# Control.net
KiCad netlist of a schematic drawn in Altium Designer
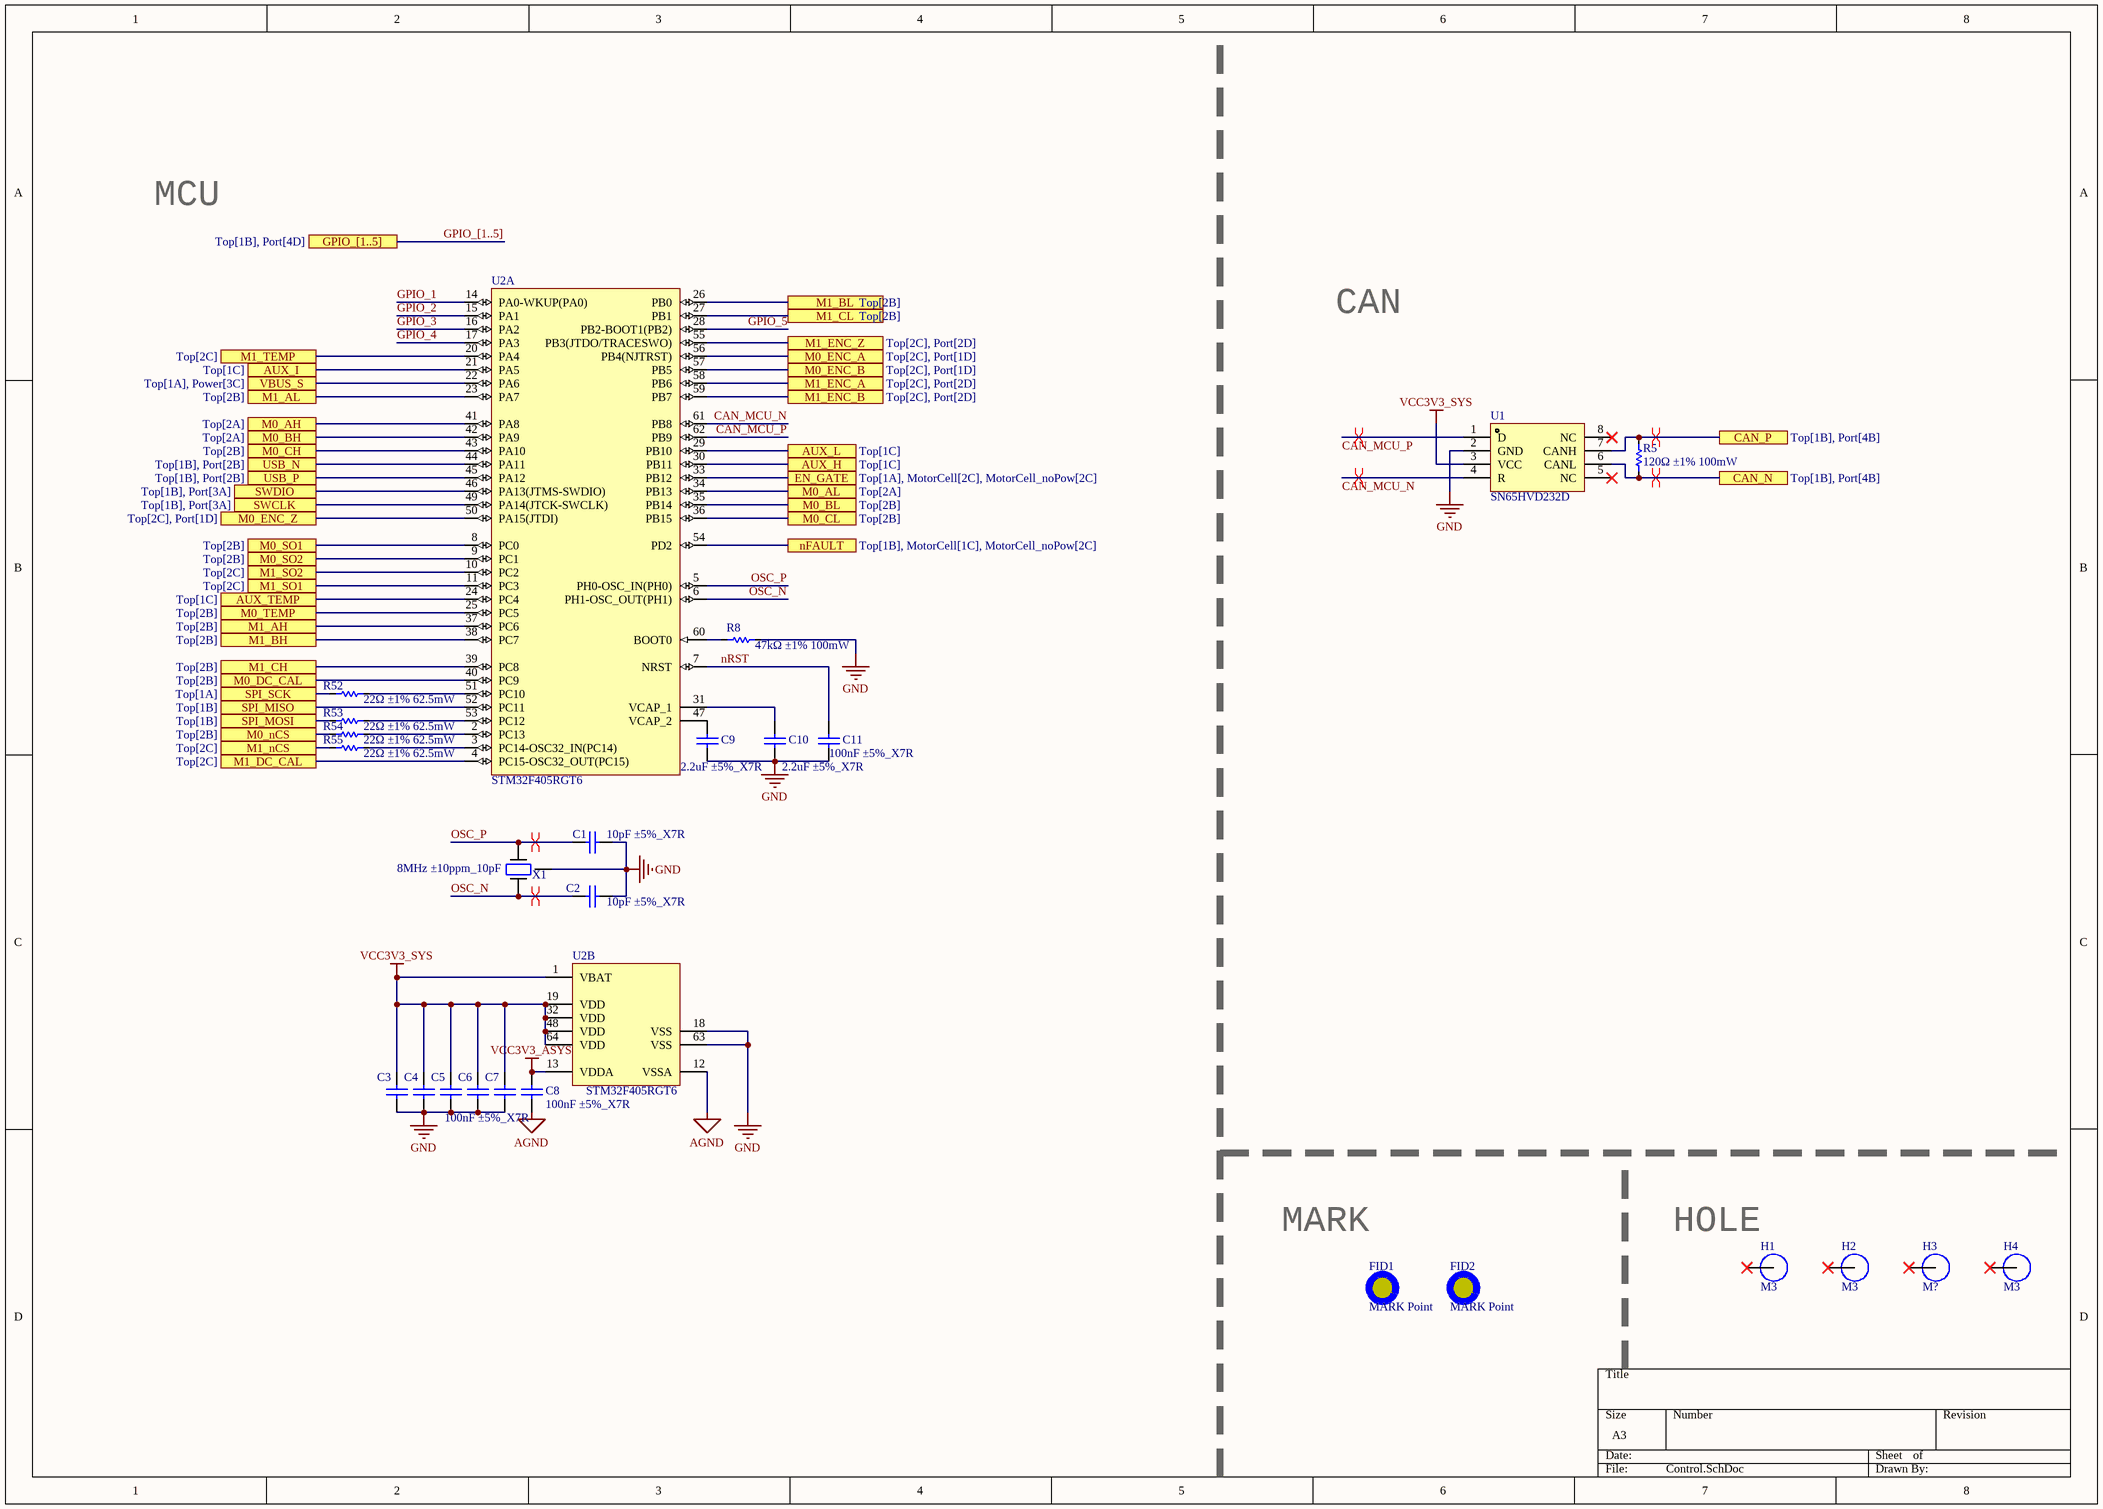
[diagram p0: Control.SchDoc]

(export (version "E")
  (design (tool "Eeschema 10.0.6"))
  (components
    (comp (ref "C1")
      (value "10pF ±5%_X7R")
      (footprint "C0402")
      (description "Capacitor")
      (fields (field (name "PUBLISHER") "Altium Limited"))
      (libsource (lib "Component") (part "Cap"))
    )
    (comp (ref "C2")
      (value "10pF ±5%_X7R")
      (footprint "C0402")
      (description "Capacitor")
      (fields (field (name "PUBLISHER") "Altium Limited"))
      (libsource (lib "Component") (part "Cap"))
    )
    (comp (ref "C3")
      (value "100nF ±5%_X7R")
      (footprint "C0402")
      (description "Capacitor")
      (fields (field (name "PUBLISHER") "Altium Limited"))
      (libsource (lib "Component") (part "Cap"))
    )
    (comp (ref "C4")
      (value "100nF ±5%_X7R")
      (footprint "C0402")
      (description "Capacitor")
      (fields (field (name "PUBLISHER") "Altium Limited"))
      (libsource (lib "Component") (part "Cap"))
    )
    (comp (ref "C5")
      (value "F ±5%_X7R")
      (footprint "C0402")
      (description "Capacitor")
      (fields (field (name "PUBLISHER") "Altium Limited"))
      (libsource (lib "Component") (part "Cap"))
    )
    (comp (ref "C6")
      (value "F ±5%_X7R")
      (footprint "C0402")
      (description "Capacitor")
      (fields (field (name "PUBLISHER") "Altium Limited"))
      (libsource (lib "Component") (part "Cap"))
    )
    (comp (ref "C7")
      (value "F ±5%_X7R")
      (footprint "C0402")
      (description "Capacitor")
      (fields (field (name "PUBLISHER") "Altium Limited"))
      (libsource (lib "Component") (part "Cap"))
    )
    (comp (ref "C8")
      (value "100nF ±5%_X7R")
      (footprint "C0402")
      (description "Capacitor")
      (fields (field (name "PUBLISHER") "Altium Limited"))
      (libsource (lib "Component") (part "Cap"))
    )
    (comp (ref "C9")
      (value "2.2uF ±5%_X7R")
      (footprint "C0603")
      (description "Capacitor")
      (fields (field (name "PUBLISHER") "Altium Limited"))
      (libsource (lib "Component") (part "Cap"))
    )
    (comp (ref "C10")
      (value "2.2uF ±5%_X7R")
      (footprint "C0603")
      (description "Capacitor")
      (fields (field (name "PUBLISHER") "Altium Limited"))
      (libsource (lib "Component") (part "Cap"))
    )
    (comp (ref "C11")
      (value "100nF ±5%_X7R")
      (footprint "C0402")
      (description "Capacitor")
      (fields (field (name "PUBLISHER") "Altium Limited"))
      (libsource (lib "Component") (part "Cap"))
    )
    (comp (ref "FID1")
      (value "MARK Point")
      (footprint "FIDUCIAL")
      (description "1mm Fiducial with 2mm soldermask, 3mm keepout")
      (libsource (lib "Component") (part "FIDUCIAL"))
    )
    (comp (ref "FID2")
      (value "MARK Point")
      (footprint "FIDUCIAL")
      (description "1mm Fiducial with 2mm soldermask, 3mm keepout")
      (libsource (lib "Component") (part "FIDUCIAL"))
    )
    (comp (ref "H1")
      (value "M3")
      (footprint "M3_NPTH")
      (description "Hole without copper")
      (libsource (lib "Component") (part "NPTH"))
    )
    (comp (ref "H2")
      (value "M3")
      (footprint "M3_NPTH")
      (description "Hole without copper")
      (libsource (lib "Component") (part "NPTH"))
    )
    (comp (ref "H3")
      (value "M?")
      (footprint "M3_NPTH")
      (description "Hole without copper")
      (libsource (lib "Component") (part "NPTH"))
    )
    (comp (ref "H4")
      (value "M3")
      (footprint "M3_NPTH")
      (description "Hole without copper")
      (libsource (lib "Component") (part "NPTH"))
    )
    (comp (ref "R5")
      (value "120Ω ±1% 100mW")
      (footprint "R0603")
      (description "Resistor")
      (fields (field (name "PUBLISHER") "Altium Limited"))
      (libsource (lib "Component") (part "Res"))
    )
    (comp (ref "R8")
      (value "47kΩ ±1% 100mW")
      (footprint "R0402")
      (description "Resistor")
      (fields (field (name "PUBLISHER") "Altium Limited"))
      (libsource (lib "Component") (part "Res"))
    )
    (comp (ref "R52")
      (value "22Ω ±1% 62.5mW")
      (footprint "R0402")
      (description "Resistor")
      (fields (field (name "PUBLISHER") "Altium Limited"))
      (libsource (lib "Component") (part "Res"))
    )
    (comp (ref "R53")
      (value "22Ω ±1% 62.5mW")
      (footprint "R0402")
      (description "Resistor")
      (fields (field (name "PUBLISHER") "Altium Limited"))
      (libsource (lib "Component") (part "Res"))
    )
    (comp (ref "R54")
      (value "22Ω ±1% 62.5mW")
      (footprint "R0402")
      (description "Resistor")
      (fields (field (name "PUBLISHER") "Altium Limited"))
      (libsource (lib "Component") (part "Res"))
    )
    (comp (ref "R55")
      (value "22Ω ±1% 62.5mW")
      (footprint "R0402")
      (description "Resistor")
      (fields (field (name "PUBLISHER") "Altium Limited"))
      (libsource (lib "Component") (part "Res"))
    )
    (comp (ref "U1")
      (value "SN65HVD232D")
      (footprint "SOIC127P600X175-8N")
      (fields (field (name "MANUFACTURER") "Texas Instruments"))
      (libsource (lib "IC") (part "SN65HVD232D"))
    )
    (comp (ref "U2")
      (value "STM32F405RGT6")
      (footprint "STM-LQFP64_N")
      (fields (field (name "MANUFACTURER") "STMicroelectronics"))
      (libsource (lib "STMicroelectronics STM32 F4") (part "STM32F405RGT6"))
    )
    (comp (ref "X1")
      (value "8MHz ±10ppm_10pF")
      (footprint "CRYSTAL_3225")
      (description "Crystal 8MHz ±10ppm 10pF 200 Ohm -10°C ~ 60°C Surface Mount 4-SMD, No Lead (DFN, LCC)")
      (fields
        (field (name "MANUFACTURER") "Abracon LLC")
        (field (name "MANUFACTURER PART NUMBER") "ABM3B-8.000MHZ-10-1-U-T")
      )
      (libsource (lib "Component") (part "CRYSTAL"))
    )
  )
  (nets
    (net (code "1") (name "/AUX_H") (class "Default")
      (node (ref "U2") (pin "30") (pinfunction "PB11_30") (pintype "bidirectional"))
    )
    (net (code "2") (name "/AUX_I") (class "Default")
      (node (ref "U2") (pin "21") (pinfunction "PA5_21") (pintype "bidirectional"))
    )
    (net (code "3") (name "/AUX_L") (class "Default")
      (node (ref "U2") (pin "29") (pinfunction "PB10_29") (pintype "bidirectional"))
    )
    (net (code "4") (name "/AUX_TEMP") (class "Default")
      (node (ref "U2") (pin "24") (pinfunction "PC4_24") (pintype "bidirectional"))
    )
    (net (code "5") (name "/CAN_MCU_N") (class "Default")
      (node (ref "U1") (pin "4") (pinfunction "R_4") (pintype "passive"))
      (node (ref "U2") (pin "61") (pinfunction "PB8_61") (pintype "bidirectional"))
    )
    (net (code "6") (name "/CAN_MCU_P") (class "Default")
      (node (ref "U1") (pin "1") (pinfunction "D_1") (pintype "passive"))
      (node (ref "U2") (pin "62") (pinfunction "PB9_62") (pintype "bidirectional"))
    )
    (net (code "7") (name "/CAN_N") (class "Default")
      (node (ref "R5") (pin "1") (pinfunction "1_1") (pintype "passive"))
      (node (ref "U1") (pin "6") (pinfunction "CANL_6") (pintype "passive"))
    )
    (net (code "8") (name "/CAN_P") (class "Default")
      (node (ref "R5") (pin "2") (pinfunction "2_2") (pintype "passive"))
      (node (ref "U1") (pin "7") (pinfunction "CANH_7") (pintype "passive"))
    )
    (net (code "9") (name "/EN_GATE") (class "Default")
      (node (ref "U2") (pin "33") (pinfunction "PB12_33") (pintype "bidirectional"))
    )
    (net (code "10") (name "/GPIO_1") (class "Default")
      (node (ref "U2") (pin "14") (pinfunction "PA0-WKUP(PA0)_14") (pintype "bidirectional"))
    )
    (net (code "11") (name "/GPIO_2") (class "Default")
      (node (ref "U2") (pin "15") (pinfunction "PA1_15") (pintype "bidirectional"))
    )
    (net (code "12") (name "/GPIO_3") (class "Default")
      (node (ref "U2") (pin "16") (pinfunction "PA2_16") (pintype "bidirectional"))
    )
    (net (code "13") (name "/GPIO_4") (class "Default")
      (node (ref "U2") (pin "17") (pinfunction "PA3_17") (pintype "bidirectional"))
    )
    (net (code "14") (name "/GPIO_5") (class "Default")
      (node (ref "U2") (pin "28") (pinfunction "PB2-BOOT1(PB2)_28") (pintype "bidirectional"))
    )
    (net (code "16") (name "/M0_AH") (class "Default")
      (node (ref "U2") (pin "41") (pinfunction "PA8_41") (pintype "bidirectional"))
    )
    (net (code "17") (name "/M0_AL") (class "Default")
      (node (ref "U2") (pin "34") (pinfunction "PB13_34") (pintype "bidirectional"))
    )
    (net (code "18") (name "/M0_BH") (class "Default")
      (node (ref "U2") (pin "42") (pinfunction "PA9_42") (pintype "bidirectional"))
    )
    (net (code "19") (name "/M0_BL") (class "Default")
      (node (ref "U2") (pin "35") (pinfunction "PB14_35") (pintype "bidirectional"))
    )
    (net (code "20") (name "/M0_CH") (class "Default")
      (node (ref "U2") (pin "43") (pinfunction "PA10_43") (pintype "bidirectional"))
    )
    (net (code "21") (name "/M0_CL") (class "Default")
      (node (ref "U2") (pin "36") (pinfunction "PB15_36") (pintype "bidirectional"))
    )
    (net (code "22") (name "/M0_DC_CAL") (class "Default")
      (node (ref "U2") (pin "40") (pinfunction "PC9_40") (pintype "bidirectional"))
    )
    (net (code "23") (name "/M0_ENC_A") (class "Default")
      (node (ref "U2") (pin "56") (pinfunction "PB4(NJTRST)_56") (pintype "bidirectional"))
    )
    (net (code "24") (name "/M0_ENC_B") (class "Default")
      (node (ref "U2") (pin "57") (pinfunction "PB5_57") (pintype "bidirectional"))
    )
    (net (code "25") (name "/M0_ENC_Z") (class "Default")
      (node (ref "U2") (pin "50") (pinfunction "PA15(JTDI)_50") (pintype "bidirectional"))
    )
    (net (code "26") (name "/M0_SO1") (class "Default")
      (node (ref "U2") (pin "8") (pinfunction "PC0_8") (pintype "bidirectional"))
    )
    (net (code "27") (name "/M0_SO2") (class "Default")
      (node (ref "U2") (pin "9") (pinfunction "PC1_9") (pintype "bidirectional"))
    )
    (net (code "28") (name "/M0_TEMP") (class "Default")
      (node (ref "U2") (pin "25") (pinfunction "PC5_25") (pintype "bidirectional"))
    )
    (net (code "29") (name "/M0_nCS") (class "Default")
      (node (ref "R54") (pin "1") (pinfunction "1_1") (pintype "passive"))
    )
    (net (code "30") (name "/M1_AH") (class "Default")
      (node (ref "U2") (pin "37") (pinfunction "PC6_37") (pintype "bidirectional"))
    )
    (net (code "31") (name "/M1_AL") (class "Default")
      (node (ref "U2") (pin "23") (pinfunction "PA7_23") (pintype "bidirectional"))
    )
    (net (code "32") (name "/M1_BH") (class "Default")
      (node (ref "U2") (pin "38") (pinfunction "PC7_38") (pintype "bidirectional"))
    )
    (net (code "33") (name "/M1_BL") (class "Default")
      (node (ref "U2") (pin "26") (pinfunction "PB0_26") (pintype "bidirectional"))
    )
    (net (code "34") (name "/M1_CH") (class "Default")
      (node (ref "U2") (pin "39") (pinfunction "PC8_39") (pintype "bidirectional"))
    )
    (net (code "35") (name "/M1_CL") (class "Default")
      (node (ref "U2") (pin "27") (pinfunction "PB1_27") (pintype "bidirectional"))
    )
    (net (code "36") (name "/M1_DC_CAL") (class "Default")
      (node (ref "U2") (pin "4") (pinfunction "PC15-OSC32_OUT(PC15)_4") (pintype "bidirectional"))
    )
    (net (code "37") (name "/M1_ENC_A") (class "Default")
      (node (ref "U2") (pin "58") (pinfunction "PB6_58") (pintype "bidirectional"))
    )
    (net (code "38") (name "/M1_ENC_B") (class "Default")
      (node (ref "U2") (pin "59") (pinfunction "PB7_59") (pintype "bidirectional"))
    )
    (net (code "39") (name "/M1_ENC_Z") (class "Default")
      (node (ref "U2") (pin "55") (pinfunction "PB3(JTDO/TRACESWO)_55") (pintype "bidirectional"))
    )
    (net (code "40") (name "/M1_SO1") (class "Default")
      (node (ref "U2") (pin "11") (pinfunction "PC3_11") (pintype "bidirectional"))
    )
    (net (code "41") (name "/M1_SO2") (class "Default")
      (node (ref "U2") (pin "10") (pinfunction "PC2_10") (pintype "bidirectional"))
    )
    (net (code "42") (name "/M1_TEMP") (class "Default")
      (node (ref "U2") (pin "20") (pinfunction "PA4_20") (pintype "bidirectional"))
    )
    (net (code "43") (name "/M1_nCS") (class "Default")
      (node (ref "R55") (pin "1") (pinfunction "1_1") (pintype "passive"))
    )
    (net (code "44") (name "/OSC_N") (class "Default")
      (node (ref "C2") (pin "1") (pinfunction "1_1") (pintype "passive"))
      (node (ref "U2") (pin "6") (pinfunction "PH1-OSC_OUT(PH1)_6") (pintype "bidirectional"))
      (node (ref "X1") (pin "1") (pintype "passive"))
    )
    (net (code "45") (name "/OSC_P") (class "Default")
      (node (ref "C1") (pin "1") (pinfunction "1_1") (pintype "passive"))
      (node (ref "U2") (pin "5") (pinfunction "PH0-OSC_IN(PH0)_5") (pintype "bidirectional"))
      (node (ref "X1") (pin "3") (pintype "passive"))
    )
    (net (code "46") (name "/SPI_MISO") (class "Default")
      (node (ref "U2") (pin "52") (pinfunction "PC11_52") (pintype "bidirectional"))
    )
    (net (code "47") (name "/SPI_MOSI") (class "Default")
      (node (ref "R53") (pin "1") (pinfunction "1_1") (pintype "passive"))
    )
    (net (code "48") (name "/SPI_SCK") (class "Default")
      (node (ref "R52") (pin "1") (pinfunction "1_1") (pintype "passive"))
    )
    (net (code "49") (name "/SWCLK") (class "Default")
      (node (ref "U2") (pin "49") (pinfunction "PA14(JTCK-SWCLK)_49") (pintype "bidirectional"))
    )
    (net (code "50") (name "/SWDIO") (class "Default")
      (node (ref "U2") (pin "46") (pinfunction "PA13(JTMS-SWDIO)_46") (pintype "bidirectional"))
    )
    (net (code "51") (name "/USB_N") (class "Default")
      (node (ref "U2") (pin "44") (pinfunction "PA11_44") (pintype "bidirectional"))
    )
    (net (code "52") (name "/USB_P") (class "Default")
      (node (ref "U2") (pin "45") (pinfunction "PA12_45") (pintype "bidirectional"))
    )
    (net (code "53") (name "/VBUS_S") (class "Default")
      (node (ref "U2") (pin "22") (pinfunction "PA6_22") (pintype "bidirectional"))
    )
    (net (code "54") (name "/nFAULT") (class "Default")
      (node (ref "U2") (pin "54") (pinfunction "PD2_54") (pintype "bidirectional"))
    )
    (net (code "55") (name "/nRST") (class "Default")
      (node (ref "C11") (pin "2") (pinfunction "2_2") (pintype "passive"))
      (node (ref "U2") (pin "7") (pinfunction "NRST_7") (pintype "bidirectional"))
    )
    (net (code "56") (name "AGND") (class "Default")
      (node (ref "C8") (pin "1") (pinfunction "1_1") (pintype "passive"))
      (node (ref "U2") (pin "12") (pinfunction "VSSA_12") (pintype "power_in"))
    )
    (net (code "57") (name "GND") (class "Default")
      (node (ref "C1") (pin "2") (pinfunction "2_2") (pintype "passive"))
      (node (ref "C10") (pin "1") (pinfunction "1_1") (pintype "passive"))
      (node (ref "C11") (pin "1") (pinfunction "1_1") (pintype "passive"))
      (node (ref "C2") (pin "2") (pinfunction "2_2") (pintype "passive"))
      (node (ref "C3") (pin "1") (pinfunction "1_1") (pintype "passive"))
      (node (ref "C4") (pin "1") (pinfunction "1_1") (pintype "passive"))
      (node (ref "C5") (pin "1") (pinfunction "1_1") (pintype "passive"))
      (node (ref "C6") (pin "1") (pinfunction "1_1") (pintype "passive"))
      (node (ref "C7") (pin "1") (pinfunction "1_1") (pintype "passive"))
      (node (ref "C9") (pin "1") (pinfunction "1_1") (pintype "passive"))
      (node (ref "R8") (pin "2") (pinfunction "2_2") (pintype "passive"))
      (node (ref "U1") (pin "2") (pinfunction "GND_2") (pintype "passive"))
      (node (ref "U2") (pin "18") (pinfunction "VSS_18") (pintype "power_in"))
      (node (ref "U2") (pin "63") (pinfunction "VSS_63") (pintype "power_in"))
      (node (ref "X1") (pin "G") (pintype "passive"))
    )
    (net (code "58") (name "Net-(U2A-BOOT0)") (class "Default")
      (node (ref "R8") (pin "1") (pinfunction "1_1") (pintype "passive"))
      (node (ref "U2") (pin "60") (pinfunction "BOOT0_60") (pintype "input"))
    )
    (net (code "59") (name "Net-(U2A-PC10)") (class "Default")
      (node (ref "R52") (pin "2") (pinfunction "2_2") (pintype "passive"))
      (node (ref "U2") (pin "51") (pinfunction "PC10_51") (pintype "bidirectional"))
    )
    (net (code "60") (name "Net-(U2A-PC12)") (class "Default")
      (node (ref "R53") (pin "2") (pinfunction "2_2") (pintype "passive"))
      (node (ref "U2") (pin "53") (pinfunction "PC12_53") (pintype "bidirectional"))
    )
    (net (code "61") (name "Net-(U2A-PC13)") (class "Default")
      (node (ref "R54") (pin "2") (pinfunction "2_2") (pintype "passive"))
      (node (ref "U2") (pin "2") (pinfunction "PC13_2") (pintype "bidirectional"))
    )
    (net (code "62") (name "Net-(U2A-PC14-OSC32_IN(PC14))") (class "Default")
      (node (ref "R55") (pin "2") (pinfunction "2_2") (pintype "passive"))
      (node (ref "U2") (pin "3") (pinfunction "PC14-OSC32_IN(PC14)_3") (pintype "bidirectional"))
    )
    (net (code "63") (name "Net-(U2A-VCAP_1)") (class "Default")
      (node (ref "C10") (pin "2") (pinfunction "2_2") (pintype "passive"))
      (node (ref "U2") (pin "31") (pinfunction "VCAP_1_31") (pintype "power_in"))
    )
    (net (code "64") (name "Net-(U2A-VCAP_2)") (class "Default")
      (node (ref "C9") (pin "2") (pinfunction "2_2") (pintype "passive"))
      (node (ref "U2") (pin "47") (pinfunction "VCAP_2_47") (pintype "power_in"))
    )
    (net (code "65") (name "VCC3V3_ASYS") (class "Default")
      (node (ref "C8") (pin "2") (pinfunction "2_2") (pintype "passive"))
      (node (ref "U2") (pin "13") (pinfunction "VDDA_13") (pintype "power_in"))
    )
    (net (code "66") (name "VCC3V3_SYS") (class "Default")
      (node (ref "C3") (pin "2") (pinfunction "2_2") (pintype "passive"))
      (node (ref "C4") (pin "2") (pinfunction "2_2") (pintype "passive"))
      (node (ref "C5") (pin "2") (pinfunction "2_2") (pintype "passive"))
      (node (ref "C6") (pin "2") (pinfunction "2_2") (pintype "passive"))
      (node (ref "C7") (pin "2") (pinfunction "2_2") (pintype "passive"))
      (node (ref "U1") (pin "3") (pinfunction "VCC_3") (pintype "passive"))
      (node (ref "U2") (pin "1") (pinfunction "VBAT_1") (pintype "power_in"))
      (node (ref "U2") (pin "19") (pinfunction "VDD_19") (pintype "power_in"))
      (node (ref "U2") (pin "32") (pinfunction "VDD_32") (pintype "power_in"))
      (node (ref "U2") (pin "48") (pinfunction "VDD_48") (pintype "power_in"))
      (node (ref "U2") (pin "64") (pinfunction "VDD_64") (pintype "power_in"))
    )
    (net (code "67") (name "unconnected-(H1-Pad1)") (class "Default")
      (node (ref "H1") (pin "1") (pinfunction "1_1") (pintype "passive+no_connect"))
    )
    (net (code "68") (name "unconnected-(H2-Pad1)") (class "Default")
      (node (ref "H2") (pin "1") (pinfunction "1_1") (pintype "passive+no_connect"))
    )
    (net (code "69") (name "unconnected-(H3-Pad1)") (class "Default")
      (node (ref "H3") (pin "1") (pinfunction "1_1") (pintype "passive+no_connect"))
    )
    (net (code "70") (name "unconnected-(H4-Pad1)") (class "Default")
      (node (ref "H4") (pin "1") (pinfunction "1_1") (pintype "passive+no_connect"))
    )
    (net (code "71") (name "unconnected-(U1-NC-Pad5)") (class "Default")
      (node (ref "U1") (pin "5") (pinfunction "NC_5") (pintype "passive+no_connect"))
    )
    (net (code "72") (name "unconnected-(U1-NC-Pad8)") (class "Default")
      (node (ref "U1") (pin "8") (pinfunction "NC_8") (pintype "passive+no_connect"))
    )
  )
)
